# Motor_Driver_1.net
KiCad netlist of a schematic drawn in Altium Designer
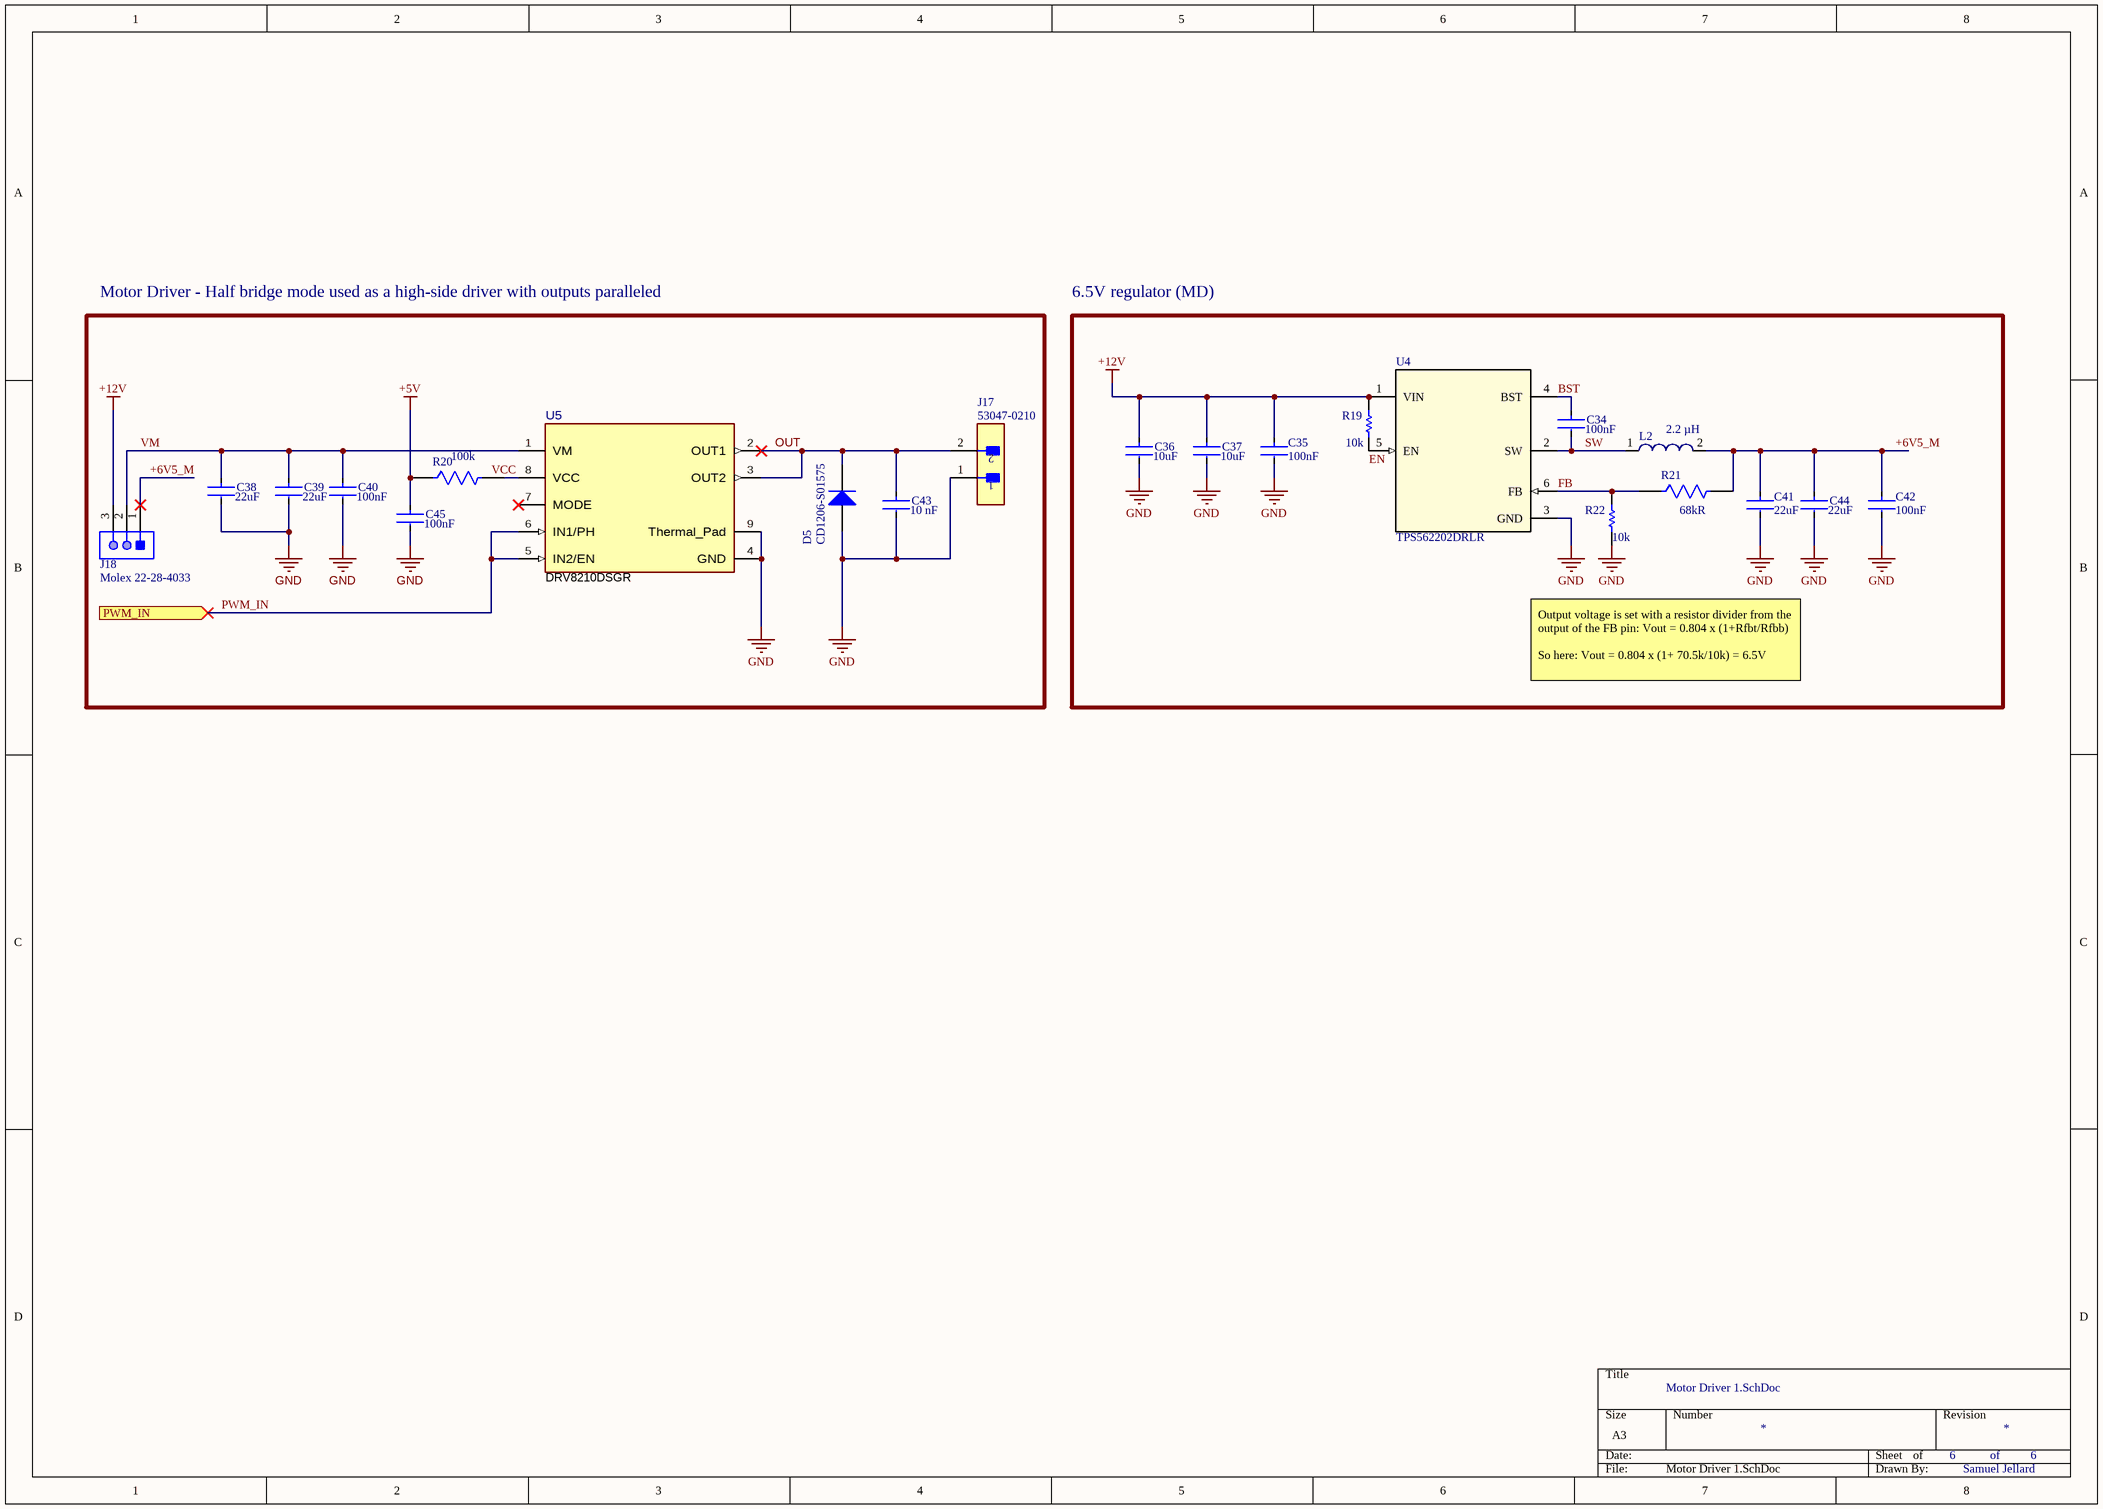
[diagram p0: Motor Driver 1.SchDoc]

(export (version "E")
  (design (tool "Eeschema 10.0.6"))
  (components
    (comp (ref "C34")
      (value "C1608X7R1E104K080AA")
      (footprint "FP-C1608-080-0_1-IPC_B")
      (description "Multilayer Ceramic Capacitors 100nF ±10% 25V X7R SMD 0603")
      (fields
        (field (name "TOLERANCE") "10%")
        (field (name "CAPACITANCE") "100nF")
        (field (name "VOLTAGE") "25V")
      )
      (libsource (lib "Altium Content Vault") (part "236180d848d6139a670b325ea6854c9"))
    )
    (comp (ref "C35")
      (value "C1608X7R1E104K080AA")
      (footprint "FP-C1608-080-0_1-IPC_B")
      (description "Multilayer Ceramic Capacitors 100nF ±10% 25V X7R SMD 0603")
      (fields
        (field (name "TOLERANCE") "10%")
        (field (name "CAPACITANCE") "100nF")
        (field (name "VOLTAGE") "25V")
      )
      (libsource (lib "Altium Content Vault") (part "236180d848d6139a670b325ea6854c9"))
    )
    (comp (ref "C36")
      (value "GRM21BR61E106MA73")
      (footprint "FP-GRM21B-0_15-IPC_A")
      (description "Chip Multilayer Ceramic Capacitors for General Purpose, 0805, 10uF, X5R, 15%, 20%, 25V")
      (fields (field (name "TOLERANCE") "20%") (field (name "CAPACITANCE") "10uF"))
      (libsource (lib "Altium Content Vault") (part "b4654b650e69147ec39a6b967a45e02"))
    )
    (comp (ref "C37")
      (value "GRM21BR61E106MA73")
      (footprint "FP-GRM21B-0_15-IPC_A")
      (description "Chip Multilayer Ceramic Capacitors for General Purpose, 0805, 10uF, X5R, 15%, 20%, 25V")
      (fields (field (name "TOLERANCE") "20%") (field (name "CAPACITANCE") "10uF"))
      (libsource (lib "Altium Content Vault") (part "b4654b650e69147ec39a6b967a45e02"))
    )
    (comp (ref "C38")
      (value "22uF")
      (footprint "FP-GRM32-MFG")
      (description "CAP CER 22UF 25V X5R 1210")
      (fields
        (field (name "TOLERANCE") "10%")
        (field (name "MANUFACTURER") "Murata Electronics North America")
      )
      (libsource (lib "Altium Content Vault") (part "11868f565c42a9108669ba33697ecf6"))
    )
    (comp (ref "C39")
      (value "22uF")
      (footprint "FP-GRM32-MFG")
      (description "CAP CER 22UF 25V X5R 1210")
      (fields
        (field (name "TOLERANCE") "10%")
        (field (name "MANUFACTURER") "Murata Electronics North America")
      )
      (libsource (lib "Altium Content Vault") (part "11868f565c42a9108669ba33697ecf6"))
    )
    (comp (ref "C40")
      (value "C0603C104Z3VACTU")
      (footprint "FP-C0603-CG-IPC_B")
      (description "KEMET C0603C104Z3VACTU / CAP .10UF 25V CERAMIC Y5V 0603")
      (fields
        (field (name "CAPACITANCE") "100nF")
        (field (name "TOLERANCE") "80%")
        (field (name "VOLTAGE") "25V")
      )
      (libsource (lib "Altium Content Vault") (part "02cd4be3c70576c341d710602a673aa"))
    )
    (comp (ref "C41")
      (value "GRM21BR61A226ME44")
      (footprint "FP-GRM21B-0_2-e0_2_0_7-IPC_C")
      (description "Chip Multilayer Ceramic Capacitors for General Purpose, 0805, 22uF, X5R, 15%, 20%, 10V")
      (fields
        (field (name "TOLERANCE") "20%")
        (field (name "VOLTAGE") "10V")
        (field (name "CAPACITANCE") "22uF")
      )
      (libsource (lib "Altium Content Vault") (part "b4654b650e69147ec39a6b967a45e02"))
    )
    (comp (ref "C42")
      (value "C1608X7R1E104K080AA")
      (footprint "FP-C1608-080-0_1-IPC_B")
      (description "Multilayer Ceramic Capacitors 100nF ±10% 25V X7R SMD 0603")
      (fields
        (field (name "TOLERANCE") "10%")
        (field (name "CAPACITANCE") "100nF")
        (field (name "VOLTAGE") "25V")
      )
      (libsource (lib "Altium Content Vault") (part "236180d848d6139a670b325ea6854c9"))
    )
    (comp (ref "C43")
      (value "10 nF")
      (footprint "FP-CC0603-DA-MFG")
      (description "SMD Multilayer Ceramic Capacitor, 10000 pF, 50 V, 0603 [1608 Metric], ± 10%, X7R,")
      (fields (field (name "TOLERANCE") "0.1") (field (name "MANUFACTURER PART NUMBER") "CC0603KRX7R9BB103"))
      (libsource (lib "Altium Content Vault") (part "11868f565c42a9108669ba33697ecf6"))
    )
    (comp (ref "C44")
      (value "GRM21BR61A226ME44")
      (footprint "FP-GRM21B-0_2-e0_2_0_7-IPC_C")
      (description "Chip Multilayer Ceramic Capacitors for General Purpose, 0805, 22uF, X5R, 15%, 20%, 10V")
      (fields
        (field (name "TOLERANCE") "20%")
        (field (name "VOLTAGE") "10V")
        (field (name "CAPACITANCE") "22uF")
      )
      (libsource (lib "Altium Content Vault") (part "b4654b650e69147ec39a6b967a45e02"))
    )
    (comp (ref "C45")
      (value "C0603C104Z3VACTU")
      (footprint "FP-C0603-CG-IPC_B")
      (description "KEMET C0603C104Z3VACTU / CAP .10UF 25V CERAMIC Y5V 0603")
      (fields
        (field (name "CAPACITANCE") "100nF")
        (field (name "TOLERANCE") "80%")
        (field (name "VOLTAGE") "25V")
      )
      (libsource (lib "Altium Content Vault") (part "02cd4be3c70576c341d710602a673aa"))
    )
    (comp (ref "D5")
      (value "CD1206-S01575")
      (footprint "BOUR-CD1206-S01575-2_L")
      (description "75 V Small Signal Switching Diode, 150 mA, 2.5 uA, 1026 Molded Package, RoHS, Tape and Reel")
      (fields (field (name "MANUFACTURER") "Bourns"))
      (libsource (lib "Altium Content Vault") (part "BOUR-A1K2-2"))
    )
    (comp (ref "J17")
      (value "53047-0210")
      (footprint "FP-53047-0210-MFG")
      (description "1.25mm (.049\") Pitch PicoBlade Wire-to-Board Header, Vertical, with Friction Lock, 2 Circuits")
      (fields
        (field (name "OCTOPART") "https://octopart.com/53047-0210-molex-276772")
        (field (name "MANUFACTURER") "Molex")
      )
      (libsource (lib "Altium Content Vault") (part "3bc925449376181038e59eaffc5286c"))
    )
    (comp (ref "J18")
      (value "Molex 22-28-4033")
      (footprint "MOLX-22-28-4033_V")
      (description "Conn.; Rect./PCB; Header; 3 Cir.; Vertical; KK/254 Series; Gold Plating")
      (fields (field (name "MANUFACTURER") "Molex"))
      (libsource (lib "Altium Content Vault") (part "CN-1P-M-R3"))
    )
    (comp (ref "L2")
      (value "74437349022")
      (footprint "WE-LHMI 7050")
      (description "SMD Power Inductor WE-LHMI, L=2.2 µH")
      (fields (field (name "INDUCTANCE") "2.2 µH") (field (name "MANUFACTURER") "Wuerth Elektronik"))
      (libsource (lib "Altium Content Vault") (part "WE-IND-INDUCTOR-2"))
    )
    (comp (ref "R19")
      (value "CRCW060310K0FKEA")
      (footprint "RESC1609X50X30NL8T20")
      (description "Chip Resistor, 10 KOhm, +/- 1%, 100 mW, -55 to 155 degC, 0603 (1608 Metric), RoHS, Tape and Reel")
      (fields (field (name "MANUFACTURER") "Vishay Semiconductor"))
      (libsource (lib "Altium Content Vault") (part "RES-2"))
    )
    (comp (ref "R20")
      (value "CRCW0603100KFKEA")
      (footprint "FP-CRCW0603-e3-IPC_C")
      (description "RES Thick Film, 100kΩ, 1%, 0.1W, 100ppm/°C, 0603")
      (fields (field (name "TOLERANCE") "1%") (field (name "RESISTANCE") "100k"))
      (libsource (lib "Altium Content Vault") (part "1029c3af85768c4190bb7ad29bc67b5"))
    )
    (comp (ref "R21")
      (value "CRCW060368K0FKEA")
      (footprint "FP-CRCW0603-e3-MFG")
      (description "RES Thick Film, 68kΩ, 1%, 0.1W, 100ppm/°C, 0603")
      (fields (field (name "TOLERANCE") "1%") (field (name "RESISTANCE") "68kR"))
      (libsource (lib "Altium Content Vault") (part "1029c3af85768c4190bb7ad29bc67b5"))
    )
    (comp (ref "R22")
      (value "CRCW060310K0FKEA")
      (footprint "RESC1609X50X30NL8T20")
      (description "Chip Resistor, 10 KOhm, +/- 1%, 100 mW, -55 to 155 degC, 0603 (1608 Metric), RoHS, Tape and Reel")
      (fields (field (name "MANUFACTURER") "Vishay Semiconductor"))
      (libsource (lib "Altium Content Vault") (part "RES-2"))
    )
    (comp (ref "U4")
      (value "TPS562202DRLR")
      (footprint "TPS562202DRLR:DRL0006A")
      (fields (field (name "COPYRIGHT") "Copyright (C) 2021 Ultra Librarian. All rights reserved."))
      (libsource (lib "TPS562202DRLR") (part "TPS562202DRLR"))
    )
    (comp (ref "U5")
      (value "SYM-DRV8210DSG")
      (footprint "DRV8212 footprint library:DSG0008A-MFG")
      (description "11V, 1A H-bridge motor driver, PWM, PH/EN, ½ bridge control, with low power sleep mode")
      (fields
        (field (name "MANUFACTURER") "Texas Instruments")
        (field (name "PARTNUMBER") "DRV8210DSGR")
        (field (name "PART NUMBER") "DRV8210DSG")
      )
      (libsource (lib "altium-import") (part "root_0_SYM-DRV8210DSG_"))
    )
  )
  (nets
    (net (code "1") (name "+5V") (class "Default")
      (node (ref "C45") (pin "1") (pinfunction "1_1") (pintype "passive"))
      (node (ref "R20") (pin "1") (pinfunction "1_1") (pintype "passive"))
    )
    (net (code "2") (name "+12V") (class "Default")
      (node (ref "C35") (pin "2") (pinfunction "2_2") (pintype "passive"))
      (node (ref "C36") (pin "1") (pinfunction "1_1") (pintype "passive"))
      (node (ref "C37") (pin "1") (pinfunction "1_1") (pintype "passive"))
      (node (ref "J18") (pin "3") (pinfunction "3_3") (pintype "passive"))
      (node (ref "R19") (pin "2") (pinfunction "2_2") (pintype "passive"))
      (node (ref "U4") (pin "1") (pinfunction "VIN_1") (pintype "power_in"))
    )
    (net (code "3") (name "/+6V5_M") (class "Default")
      (node (ref "C41") (pin "1") (pinfunction "1_1") (pintype "passive"))
      (node (ref "C42") (pin "2") (pinfunction "2_2") (pintype "passive"))
      (node (ref "C44") (pin "1") (pinfunction "1_1") (pintype "passive"))
      (node (ref "J18") (pin "1") (pinfunction "1_1") (pintype "passive"))
      (node (ref "L2") (pin "2") (pinfunction "2_2") (pintype "passive"))
      (node (ref "R21") (pin "2") (pinfunction "2_2") (pintype "passive"))
    )
    (net (code "4") (name "/BST") (class "Default")
      (node (ref "C34") (pin "2") (pinfunction "2_2") (pintype "passive"))
      (node (ref "U4") (pin "4") (pinfunction "BST_4") (pintype "passive"))
    )
    (net (code "5") (name "/EN") (class "Default")
      (node (ref "R19") (pin "1") (pinfunction "1_1") (pintype "passive"))
      (node (ref "U4") (pin "5") (pinfunction "EN_5") (pintype "input"))
    )
    (net (code "6") (name "/FB") (class "Default")
      (node (ref "R21") (pin "1") (pinfunction "1_1") (pintype "passive"))
      (node (ref "R22") (pin "2") (pinfunction "2_2") (pintype "passive"))
      (node (ref "U4") (pin "6") (pinfunction "FB_6") (pintype "input"))
    )
    (net (code "7") (name "/OUT") (class "Default")
      (node (ref "C43") (pin "1") (pinfunction "1_1") (pintype "passive"))
      (node (ref "D5") (pin "2") (pinfunction "K_2") (pintype "passive"))
      (node (ref "J17") (pin "2") (pinfunction "2_2") (pintype "passive"))
      (node (ref "U5") (pin "2") (pinfunction "OUT1_2") (pintype "output"))
      (node (ref "U5") (pin "3") (pinfunction "OUT2_3") (pintype "output"))
    )
    (net (code "8") (name "/PWM_IN") (class "Default")
      (node (ref "U5") (pin "5") (pinfunction "IN2/EN_5") (pintype "input"))
      (node (ref "U5") (pin "6") (pinfunction "IN1/PH_6") (pintype "input"))
    )
    (net (code "9") (name "/SW") (class "Default")
      (node (ref "C34") (pin "1") (pinfunction "1_1") (pintype "passive"))
      (node (ref "L2") (pin "1") (pinfunction "1_1") (pintype "passive"))
      (node (ref "U4") (pin "2") (pinfunction "SW_2") (pintype "power_in"))
    )
    (net (code "11") (name "/VM") (class "Default")
      (node (ref "C38") (pin "1") (pinfunction "1_1") (pintype "passive"))
      (node (ref "C39") (pin "1") (pinfunction "1_1") (pintype "passive"))
      (node (ref "C40") (pin "1") (pinfunction "1_1") (pintype "passive"))
      (node (ref "J18") (pin "2") (pinfunction "2_2") (pintype "passive"))
      (node (ref "U5") (pin "1") (pinfunction "VM_1") (pintype "power_in"))
    )
    (net (code "12") (name "GND") (class "Default")
      (node (ref "C35") (pin "1") (pinfunction "1_1") (pintype "passive"))
      (node (ref "C36") (pin "2") (pinfunction "2_2") (pintype "passive"))
      (node (ref "C37") (pin "2") (pinfunction "2_2") (pintype "passive"))
      (node (ref "C38") (pin "2") (pinfunction "2_2") (pintype "passive"))
      (node (ref "C39") (pin "2") (pinfunction "2_2") (pintype "passive"))
      (node (ref "C40") (pin "2") (pinfunction "2_2") (pintype "passive"))
      (node (ref "C41") (pin "2") (pinfunction "2_2") (pintype "passive"))
      (node (ref "C42") (pin "1") (pinfunction "1_1") (pintype "passive"))
      (node (ref "C43") (pin "2") (pinfunction "2_2") (pintype "passive"))
      (node (ref "C44") (pin "2") (pinfunction "2_2") (pintype "passive"))
      (node (ref "C45") (pin "2") (pinfunction "2_2") (pintype "passive"))
      (node (ref "D5") (pin "1") (pinfunction "A_1") (pintype "passive"))
      (node (ref "J17") (pin "1") (pinfunction "1_1") (pintype "passive"))
      (node (ref "R22") (pin "1") (pinfunction "1_1") (pintype "passive"))
      (node (ref "U4") (pin "3") (pinfunction "GND_3") (pintype "power_in"))
      (node (ref "U5") (pin "4") (pinfunction "GND_4") (pintype "power_in"))
      (node (ref "U5") (pin "9") (pinfunction "Thermal_Pad_9") (pintype "power_in"))
    )
    (net (code "13") (name "Net-(U5-VCC)") (class "Default")
      (node (ref "R20") (pin "2") (pinfunction "2_2") (pintype "passive"))
      (node (ref "U5") (pin "8") (pinfunction "VCC_8") (pintype "power_in"))
    )
    (net (code "14") (name "unconnected-(U5-MODE-Pad7)") (class "Default")
      (node (ref "U5") (pin "7") (pinfunction "MODE_7") (pintype "passive+no_connect"))
    )
  )
)
